# SAMA7D65_DDR3L.net
KiCad netlist of a schematic drawn in Altium Designer
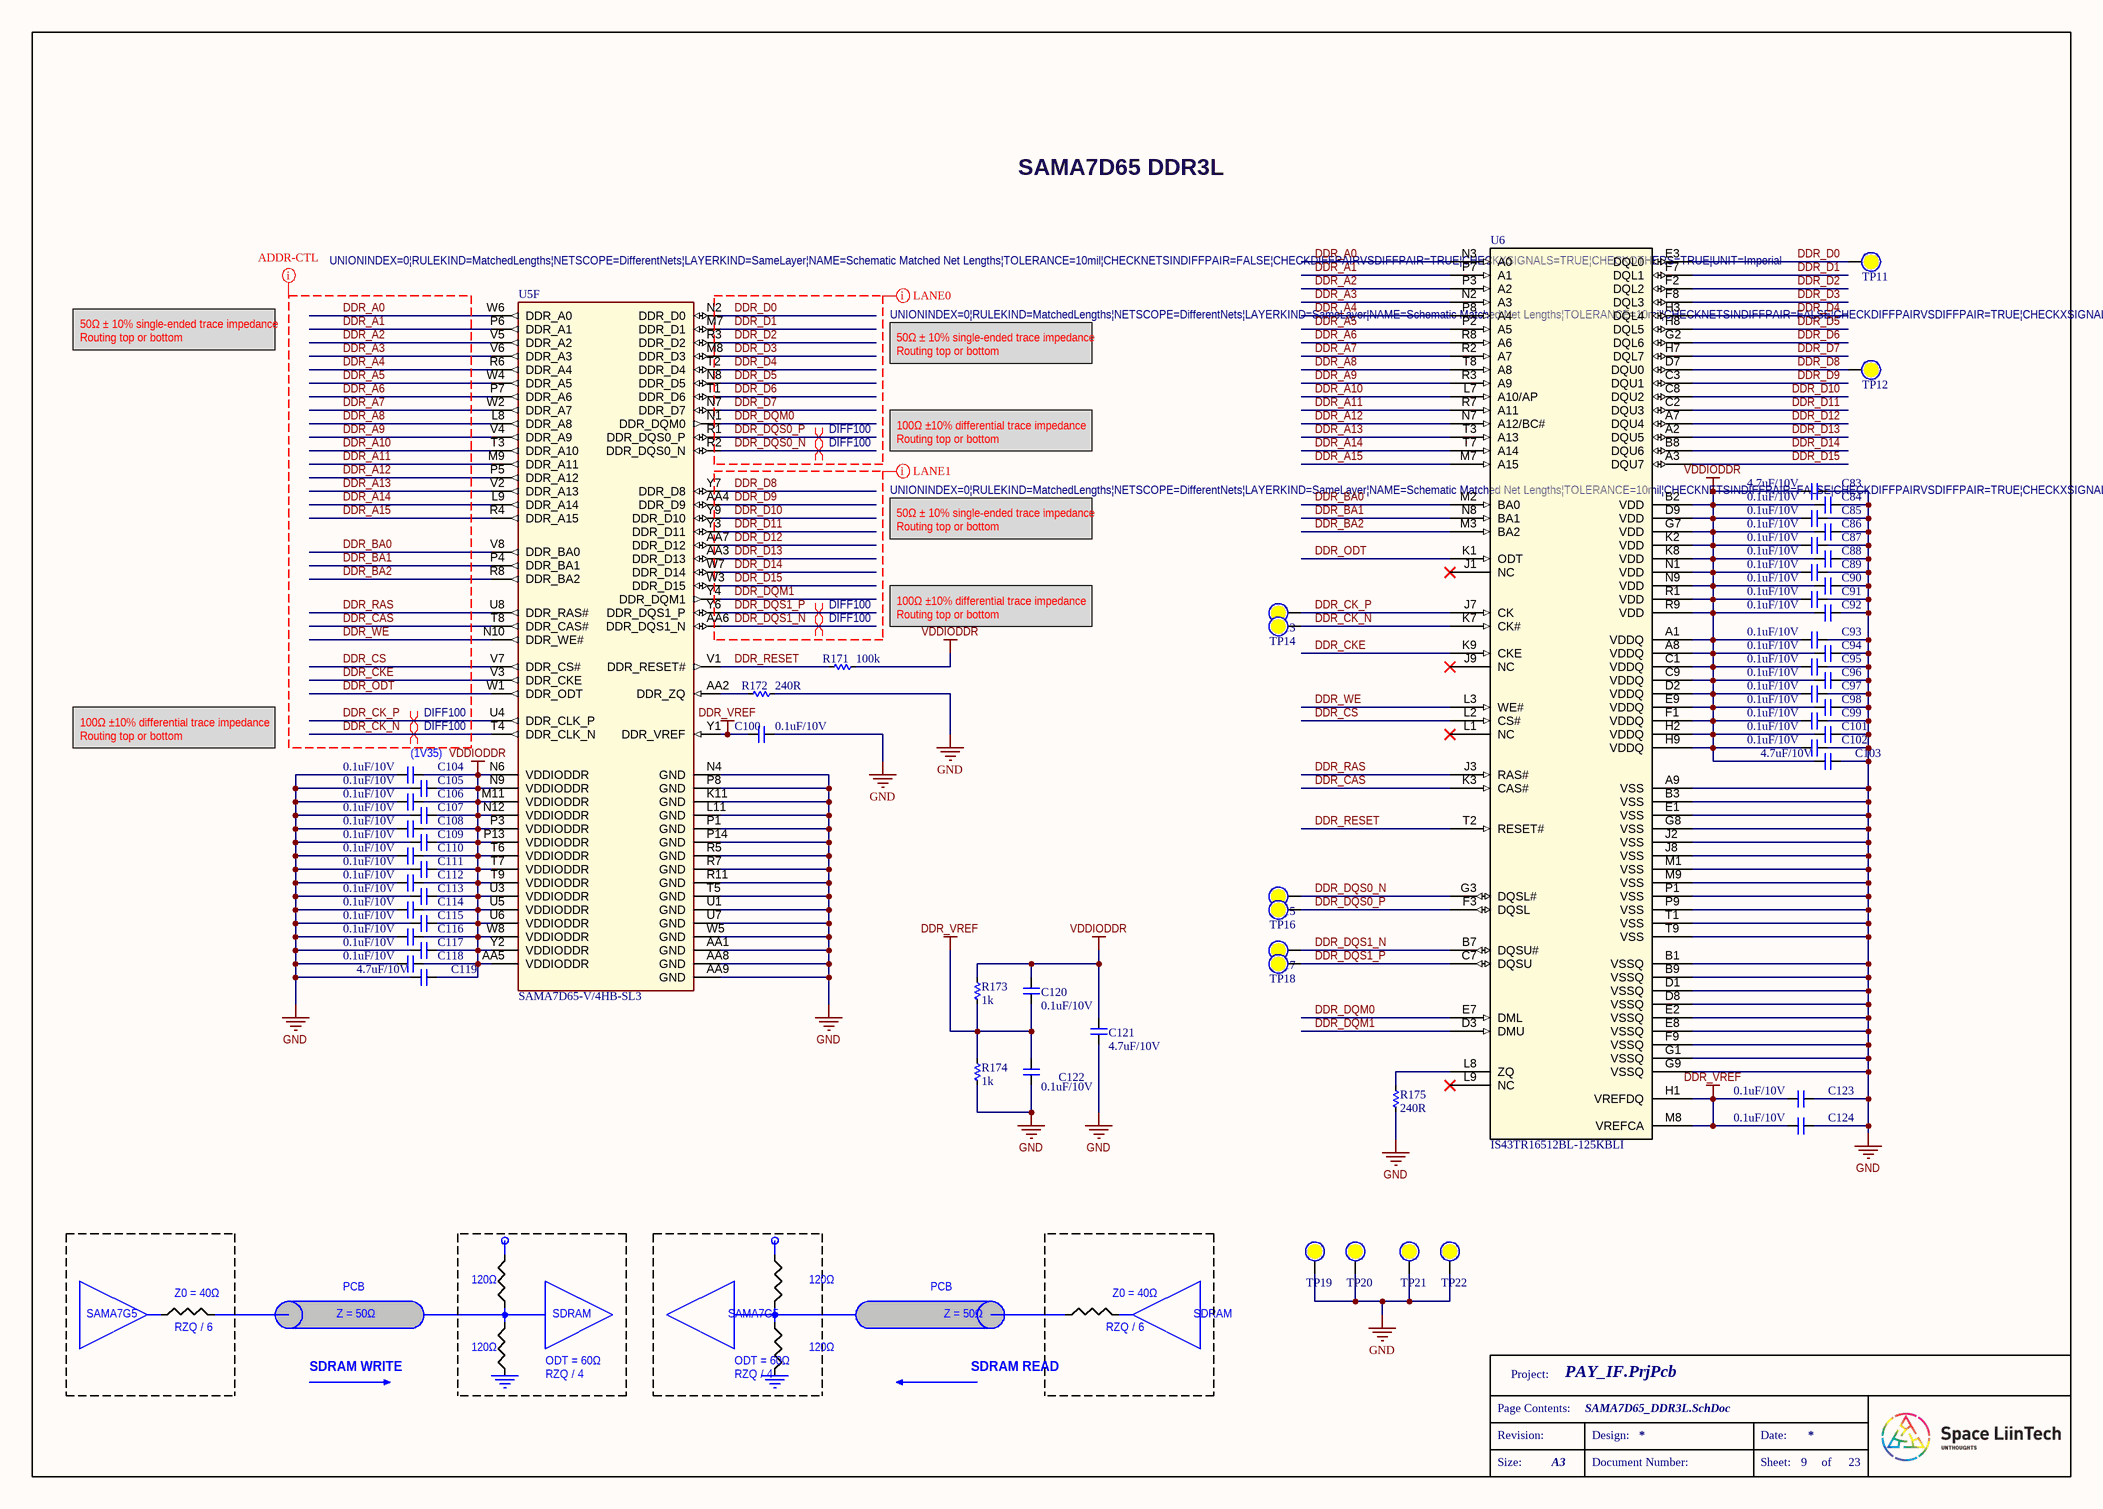
[diagram p0: SAMA7D65_DDR3L.SchDoc]

(export (version "E")
  (design (tool "Eeschema 10.0.6"))
  (components
    (comp (ref "C83")
      (value "4.7uF/10V")
      (footprint "CAP_C_1005X50_L")
      (description "CAP CHIP")
      (libsource (lib "IFBschelib") (part "_CAP_C_2"))
    )
    (comp (ref "C84")
      (value "0.1uF/10V")
      (footprint "CAP_C_0603x30")
      (description "CAP CHIP")
      (libsource (lib "IFBschelib") (part "_CAP_C_2"))
    )
    (comp (ref "C85")
      (value "0.1uF/10V")
      (footprint "CAP_C_0603x30")
      (description "CAP CHIP")
      (libsource (lib "IFBschelib") (part "_CAP_C_2"))
    )
    (comp (ref "C86")
      (value "0.1uF/10V")
      (footprint "CAP_C_0603x30")
      (description "CAP CHIP")
      (libsource (lib "IFBschelib") (part "_CAP_C_2"))
    )
    (comp (ref "C87")
      (value "0.1uF/10V")
      (footprint "CAP_C_0603x30")
      (description "CAP CHIP")
      (libsource (lib "IFBschelib") (part "_CAP_C_2"))
    )
    (comp (ref "C88")
      (value "0.1uF/10V")
      (footprint "CAP_C_0603x30")
      (description "CAP CHIP")
      (libsource (lib "IFBschelib") (part "_CAP_C_2"))
    )
    (comp (ref "C89")
      (value "0.1uF/10V")
      (footprint "CAP_C_0603x30")
      (description "CAP CHIP")
      (libsource (lib "IFBschelib") (part "_CAP_C_2"))
    )
    (comp (ref "C90")
      (value "0.1uF/10V")
      (footprint "CAP_C_0603x30")
      (description "CAP CHIP")
      (libsource (lib "IFBschelib") (part "_CAP_C_2"))
    )
    (comp (ref "C91")
      (value "0.1uF/10V")
      (footprint "CAP_C_0603x30")
      (description "CAP CHIP")
      (libsource (lib "IFBschelib") (part "_CAP_C_2"))
    )
    (comp (ref "C92")
      (value "0.1uF/10V")
      (footprint "CAP_C_0603x30")
      (description "CAP CHIP")
      (libsource (lib "IFBschelib") (part "_CAP_C_2"))
    )
    (comp (ref "C93")
      (value "0.1uF/10V")
      (footprint "CAP_C_0603x30")
      (description "CAP CHIP")
      (libsource (lib "IFBschelib") (part "_CAP_C_2"))
    )
    (comp (ref "C94")
      (value "0.1uF/10V")
      (footprint "CAP_C_0603x30")
      (description "CAP CHIP")
      (libsource (lib "IFBschelib") (part "_CAP_C_2"))
    )
    (comp (ref "C95")
      (value "0.1uF/10V")
      (footprint "CAP_C_0603x30")
      (description "CAP CHIP")
      (libsource (lib "IFBschelib") (part "_CAP_C_2"))
    )
    (comp (ref "C96")
      (value "0.1uF/10V")
      (footprint "CAP_C_0603x30")
      (description "CAP CHIP")
      (libsource (lib "IFBschelib") (part "_CAP_C_2"))
    )
    (comp (ref "C97")
      (value "0.1uF/10V")
      (footprint "CAP_C_0603x30")
      (description "CAP CHIP")
      (libsource (lib "IFBschelib") (part "_CAP_C_2"))
    )
    (comp (ref "C98")
      (value "0.1uF/10V")
      (footprint "CAP_C_0603x30")
      (description "CAP CHIP")
      (libsource (lib "IFBschelib") (part "_CAP_C_2"))
    )
    (comp (ref "C99")
      (value "0.1uF/10V")
      (footprint "CAP_C_0603x30")
      (description "CAP CHIP")
      (libsource (lib "IFBschelib") (part "_CAP_C_2"))
    )
    (comp (ref "C100")
      (value "0.1uF/10V")
      (footprint "CAP_C_0603x30")
      (description "CAP CHIP")
      (libsource (lib "IFBschelib") (part "_CAP_C_2"))
    )
    (comp (ref "C101")
      (value "0.1uF/10V")
      (footprint "CAP_C_0603x30")
      (description "CAP CHIP")
      (libsource (lib "IFBschelib") (part "_CAP_C_2"))
    )
    (comp (ref "C102")
      (value "0.1uF/10V")
      (footprint "CAP_C_0603x30")
      (description "CAP CHIP")
      (libsource (lib "IFBschelib") (part "_CAP_C_2"))
    )
    (comp (ref "C103")
      (value "4.7uF/10V")
      (footprint "CAP_C_1005X50_L")
      (description "CAP CHIP")
      (libsource (lib "IFBschelib") (part "_CAP_C_2"))
    )
    (comp (ref "C104")
      (value "0.1uF/10V")
      (footprint "CAP_C_0603x30")
      (description "CAP CHIP")
      (libsource (lib "IFBschelib") (part "_CAP_C_2"))
    )
    (comp (ref "C105")
      (value "0.1uF/10V")
      (footprint "CAP_C_0603x30")
      (description "CAP CHIP")
      (libsource (lib "IFBschelib") (part "_CAP_C_2"))
    )
    (comp (ref "C106")
      (value "0.1uF/10V")
      (footprint "CAP_C_0603x30")
      (description "CAP CHIP")
      (libsource (lib "IFBschelib") (part "_CAP_C_2"))
    )
    (comp (ref "C107")
      (value "0.1uF/10V")
      (footprint "CAP_C_0603x30")
      (description "CAP CHIP")
      (libsource (lib "IFBschelib") (part "_CAP_C_2"))
    )
    (comp (ref "C108")
      (value "0.1uF/10V")
      (footprint "CAP_C_0603x30")
      (description "CAP CHIP")
      (libsource (lib "IFBschelib") (part "_CAP_C_2"))
    )
    (comp (ref "C109")
      (value "0.1uF/10V")
      (footprint "CAP_C_0603x30")
      (description "CAP CHIP")
      (libsource (lib "IFBschelib") (part "_CAP_C_2"))
    )
    (comp (ref "C110")
      (value "0.1uF/10V")
      (footprint "CAP_C_0603x30")
      (description "CAP CHIP")
      (libsource (lib "IFBschelib") (part "_CAP_C_2"))
    )
    (comp (ref "C111")
      (value "0.1uF/10V")
      (footprint "CAP_C_0603x30")
      (description "CAP CHIP")
      (libsource (lib "IFBschelib") (part "_CAP_C_2"))
    )
    (comp (ref "C112")
      (value "0.1uF/10V")
      (footprint "CAP_C_0603x30")
      (description "CAP CHIP")
      (libsource (lib "IFBschelib") (part "_CAP_C_2"))
    )
    (comp (ref "C113")
      (value "0.1uF/10V")
      (footprint "CAP_C_0603x30")
      (description "CAP CHIP")
      (libsource (lib "IFBschelib") (part "_CAP_C_2"))
    )
    (comp (ref "C114")
      (value "0.1uF/10V")
      (footprint "CAP_C_0603x30")
      (description "CAP CHIP")
      (libsource (lib "IFBschelib") (part "_CAP_C_2"))
    )
    (comp (ref "C115")
      (value "0.1uF/10V")
      (footprint "CAP_C_0603x30")
      (description "CAP CHIP")
      (libsource (lib "IFBschelib") (part "_CAP_C_2"))
    )
    (comp (ref "C116")
      (value "0.1uF/10V")
      (footprint "CAP_C_0603x30")
      (description "CAP CHIP")
      (libsource (lib "IFBschelib") (part "_CAP_C_2"))
    )
    (comp (ref "C117")
      (value "0.1uF/10V")
      (footprint "CAP_C_0603x30")
      (description "CAP CHIP")
      (libsource (lib "IFBschelib") (part "_CAP_C_2"))
    )
    (comp (ref "C118")
      (value "0.1uF/10V")
      (footprint "CAP_C_0603x30")
      (description "CAP CHIP")
      (libsource (lib "IFBschelib") (part "_CAP_C_2"))
    )
    (comp (ref "C119")
      (value "4.7uF/10V")
      (footprint "CAP_C_1005X50_L")
      (description "CAP CHIP")
      (libsource (lib "IFBschelib") (part "_CAP_C_2"))
    )
    (comp (ref "C120")
      (value "0.1uF/10V")
      (footprint "CAP_C_0603x30")
      (description "CAP CHIP")
      (libsource (lib "IFBschelib") (part "_CAP_C_2"))
    )
    (comp (ref "C121")
      (value "4.7uF/10V")
      (footprint "CAP_C_1005X50_L")
      (description "CAP CHIP")
      (libsource (lib "IFBschelib") (part "_CAP_C_2"))
    )
    (comp (ref "C122")
      (value "0.1uF/10V")
      (footprint "CAP_C_0603x30")
      (description "CAP CHIP")
      (libsource (lib "IFBschelib") (part "_CAP_C_2"))
    )
    (comp (ref "C123")
      (value "0.1uF/10V")
      (footprint "CAP_C_0603x30")
      (description "CAP CHIP")
      (libsource (lib "IFBschelib") (part "_CAP_C_2"))
    )
    (comp (ref "C124")
      (value "0.1uF/10V")
      (footprint "CAP_C_0603x30")
      (description "CAP CHIP")
      (libsource (lib "IFBschelib") (part "_CAP_C_2"))
    )
    (comp (ref "R171")
      (value "100k")
      (footprint "RES_C_1005x30_L")
      (description "RES")
      (libsource (lib "IFBschelib") (part "_RES_B_2"))
    )
    (comp (ref "R172")
      (value "240R")
      (footprint "RES_C_0603X30")
      (description "RES")
      (libsource (lib "IFBschelib") (part "_RES_B_2"))
    )
    (comp (ref "R173")
      (value "1k")
      (footprint "RES_C_1005x30_L")
      (description "RES")
      (libsource (lib "IFBschelib") (part "_RES_B_2"))
    )
    (comp (ref "R174")
      (value "1k")
      (footprint "RES_C_1005x30_L")
      (description "RES")
      (libsource (lib "IFBschelib") (part "_RES_B_2"))
    )
    (comp (ref "R175")
      (value "240R")
      (footprint "RES_C_0603X30")
      (description "RES")
      (libsource (lib "IFBschelib") (part "_RES_B_2"))
    )
    (comp (ref "TP11")
      (value "~")
      (footprint "Test point")
      (description "Test Point")
      (libsource (lib "") (part "Test Point_2"))
    )
    (comp (ref "TP12")
      (value "~")
      (footprint "Test point")
      (description "Test Point")
      (libsource (lib "") (part "Test Point_2"))
    )
    (comp (ref "TP13")
      (value "~")
      (footprint "Test point")
      (description "Test Point")
      (libsource (lib "IFBschelib") (part "Test Point"))
    )
    (comp (ref "TP14")
      (value "~")
      (footprint "Test point")
      (description "Test Point")
      (libsource (lib "IFBschelib") (part "Test Point"))
    )
    (comp (ref "TP15")
      (value "~")
      (footprint "Test point")
      (description "Test Point")
      (libsource (lib "IFBschelib") (part "Test Point"))
    )
    (comp (ref "TP16")
      (value "~")
      (footprint "Test point")
      (description "Test Point")
      (libsource (lib "IFBschelib") (part "Test Point"))
    )
    (comp (ref "TP17")
      (value "~")
      (footprint "Test point")
      (description "Test Point")
      (libsource (lib "IFBschelib") (part "Test Point"))
    )
    (comp (ref "TP18")
      (value "~")
      (footprint "Test point")
      (description "Test Point")
      (libsource (lib "IFBschelib") (part "Test Point"))
    )
    (comp (ref "TP19")
      (value "~")
      (footprint "Test point")
      (description "Test Point")
      (libsource (lib "") (part "Test Point_1"))
    )
    (comp (ref "TP20")
      (value "~")
      (footprint "Test point")
      (description "Test Point")
      (libsource (lib "") (part "Test Point_1"))
    )
    (comp (ref "TP21")
      (value "~")
      (footprint "Test point")
      (description "Test Point")
      (libsource (lib "") (part "Test Point_1"))
    )
    (comp (ref "TP22")
      (value "~")
      (footprint "Test point")
      (description "Test Point")
      (libsource (lib "") (part "Test Point_1"))
    )
    (comp (ref "U5")
      (value "SAMA7D65-V/4HB-SL3")
      (footprint "TFBGA-343_14x14")
      (description "SAMA7D65 MPU 1000MHz Cortex-A7 TFBGA-343")
      (fields (field (name "Comment") "SAMA7D65") (field (name "OWNER") "Ciprian Abramov"))
      (libsource (lib "IFBschelib") (part "SAMA7D65"))
    )
    (comp (ref "U6")
      (value "IS43TR16512BL-125KBLI")
      (footprint "TWBGA96_ISI")
      (description "DDR3L")
      (fields (field (name "COPYRIGHT") "Copyright (C) 2025 Ultra Librarian. All rights reserved."))
      (libsource (lib "IFBschelib") (part "IC_RAM_IS43TR16512BL-125KBLI"))
    )
  )
  (nets
    (net (code "1") (name "/DDR_A0") (class "Default")
      (node (ref "U5") (pin "W6") (pinfunction "DDR_A0_W6") (pintype "output"))
      (node (ref "U6") (pin "N3") (pinfunction "A0_N3") (pintype "input"))
    )
    (net (code "2") (name "/DDR_A1") (class "Default")
      (node (ref "U5") (pin "P6") (pinfunction "DDR_A1_P6") (pintype "output"))
      (node (ref "U6") (pin "P7") (pinfunction "A1_P7") (pintype "input"))
    )
    (net (code "3") (name "/DDR_A2") (class "Default")
      (node (ref "U5") (pin "V5") (pinfunction "DDR_A2_V5") (pintype "output"))
      (node (ref "U6") (pin "P3") (pinfunction "A2_P3") (pintype "input"))
    )
    (net (code "4") (name "/DDR_A3") (class "Default")
      (node (ref "U5") (pin "V6") (pinfunction "DDR_A3_V6") (pintype "output"))
      (node (ref "U6") (pin "N2") (pinfunction "A3_N2") (pintype "input"))
    )
    (net (code "5") (name "/DDR_A4") (class "Default")
      (node (ref "U5") (pin "R6") (pinfunction "DDR_A4_R6") (pintype "output"))
      (node (ref "U6") (pin "P8") (pinfunction "A4_P8") (pintype "input"))
    )
    (net (code "6") (name "/DDR_A5") (class "Default")
      (node (ref "U5") (pin "W4") (pinfunction "DDR_A5_W4") (pintype "output"))
      (node (ref "U6") (pin "P2") (pinfunction "A5_P2") (pintype "input"))
    )
    (net (code "7") (name "/DDR_A6") (class "Default")
      (node (ref "U5") (pin "P7") (pinfunction "DDR_A6_P7") (pintype "output"))
      (node (ref "U6") (pin "R8") (pinfunction "A6_R8") (pintype "input"))
    )
    (net (code "8") (name "/DDR_A7") (class "Default")
      (node (ref "U5") (pin "W2") (pinfunction "DDR_A7_W2") (pintype "output"))
      (node (ref "U6") (pin "R2") (pinfunction "A7_R2") (pintype "input"))
    )
    (net (code "9") (name "/DDR_A8") (class "Default")
      (node (ref "U5") (pin "L8") (pinfunction "DDR_A8_L8") (pintype "output"))
      (node (ref "U6") (pin "T8") (pinfunction "A8_T8") (pintype "input"))
    )
    (net (code "10") (name "/DDR_A9") (class "Default")
      (node (ref "U5") (pin "V4") (pinfunction "DDR_A9_V4") (pintype "output"))
      (node (ref "U6") (pin "R3") (pinfunction "A9_R3") (pintype "input"))
    )
    (net (code "11") (name "/DDR_A10") (class "Default")
      (node (ref "U5") (pin "T3") (pinfunction "DDR_A10_T3") (pintype "output"))
      (node (ref "U6") (pin "L7") (pinfunction "A10/AP_L7") (pintype "input"))
    )
    (net (code "12") (name "/DDR_A11") (class "Default")
      (node (ref "U5") (pin "M9") (pinfunction "DDR_A11_M9") (pintype "output"))
      (node (ref "U6") (pin "R7") (pinfunction "A11_R7") (pintype "input"))
    )
    (net (code "13") (name "/DDR_A12") (class "Default")
      (node (ref "U5") (pin "P5") (pinfunction "DDR_A12_P5") (pintype "output"))
      (node (ref "U6") (pin "N7") (pinfunction "A12/BC#_N7") (pintype "input"))
    )
    (net (code "14") (name "/DDR_A13") (class "Default")
      (node (ref "U5") (pin "V2") (pinfunction "DDR_A13_V2") (pintype "output"))
      (node (ref "U6") (pin "T3") (pinfunction "A13_T3") (pintype "input"))
    )
    (net (code "15") (name "/DDR_A14") (class "Default")
      (node (ref "U5") (pin "L9") (pinfunction "DDR_A14_L9") (pintype "output"))
      (node (ref "U6") (pin "T7") (pinfunction "A14_T7") (pintype "input"))
    )
    (net (code "16") (name "/DDR_A15") (class "Default")
      (node (ref "U5") (pin "R4") (pinfunction "DDR_A15_R4") (pintype "output"))
      (node (ref "U6") (pin "M7") (pinfunction "A15_M7") (pintype "input"))
    )
    (net (code "17") (name "/DDR_BA0") (class "Default")
      (node (ref "U5") (pin "V8") (pinfunction "DDR_BA0_V8") (pintype "output"))
      (node (ref "U6") (pin "M2") (pinfunction "BA0_M2") (pintype "input"))
    )
    (net (code "18") (name "/DDR_BA1") (class "Default")
      (node (ref "U5") (pin "P4") (pinfunction "DDR_BA1_P4") (pintype "output"))
      (node (ref "U6") (pin "N8") (pinfunction "BA1_N8") (pintype "input"))
    )
    (net (code "19") (name "/DDR_BA2") (class "Default")
      (node (ref "U5") (pin "R8") (pinfunction "DDR_BA2_R8") (pintype "output"))
      (node (ref "U6") (pin "M3") (pinfunction "BA2_M3") (pintype "input"))
    )
    (net (code "20") (name "/DDR_CAS") (class "Default")
      (node (ref "U5") (pin "T8") (pinfunction "DDR_CAS#_T8") (pintype "output"))
      (node (ref "U6") (pin "K3") (pinfunction "CAS#_K3") (pintype "input"))
    )
    (net (code "21") (name "/DDR_CKE") (class "Default")
      (node (ref "U5") (pin "V3") (pinfunction "DDR_CKE_V3") (pintype "output"))
      (node (ref "U6") (pin "K9") (pinfunction "CKE_K9") (pintype "input"))
    )
    (net (code "22") (name "/DDR_CK_N") (class "Default")
      (node (ref "TP14") (pin "0") (pinfunction "0_0") (pintype "passive"))
      (node (ref "U5") (pin "T4") (pinfunction "DDR_CLK_N_T4") (pintype "output"))
      (node (ref "U6") (pin "K7") (pinfunction "CK#_K7") (pintype "input"))
    )
    (net (code "23") (name "/DDR_CK_P") (class "Default")
      (node (ref "TP13") (pin "0") (pinfunction "0_0") (pintype "passive"))
      (node (ref "U5") (pin "U4") (pinfunction "DDR_CLK_P_U4") (pintype "output"))
      (node (ref "U6") (pin "J7") (pinfunction "CK_J7") (pintype "input"))
    )
    (net (code "24") (name "/DDR_CS") (class "Default")
      (node (ref "U5") (pin "V7") (pinfunction "DDR_CS#_V7") (pintype "output"))
      (node (ref "U6") (pin "L2") (pinfunction "CS#_L2") (pintype "input"))
    )
    (net (code "25") (name "/DDR_D0") (class "Default")
      (node (ref "TP11") (pin "0") (pinfunction "0_0") (pintype "passive"))
      (node (ref "U5") (pin "N2") (pinfunction "DDR_D0_N2") (pintype "bidirectional"))
      (node (ref "U6") (pin "E3") (pinfunction "DQL0_E3") (pintype "bidirectional"))
    )
    (net (code "26") (name "/DDR_D1") (class "Default")
      (node (ref "U5") (pin "M7") (pinfunction "DDR_D1_M7") (pintype "bidirectional"))
      (node (ref "U6") (pin "F7") (pinfunction "DQL1_F7") (pintype "bidirectional"))
    )
    (net (code "27") (name "/DDR_D2") (class "Default")
      (node (ref "U5") (pin "R3") (pinfunction "DDR_D2_R3") (pintype "bidirectional"))
      (node (ref "U6") (pin "F2") (pinfunction "DQL2_F2") (pintype "bidirectional"))
    )
    (net (code "28") (name "/DDR_D3") (class "Default")
      (node (ref "U5") (pin "M8") (pinfunction "DDR_D3_M8") (pintype "bidirectional"))
      (node (ref "U6") (pin "F8") (pinfunction "DQL3_F8") (pintype "bidirectional"))
    )
    (net (code "29") (name "/DDR_D4") (class "Default")
      (node (ref "U5") (pin "T2") (pinfunction "DDR_D4_T2") (pintype "bidirectional"))
      (node (ref "U6") (pin "H3") (pinfunction "DQL4_H3") (pintype "bidirectional"))
    )
    (net (code "30") (name "/DDR_D5") (class "Default")
      (node (ref "U5") (pin "N8") (pinfunction "DDR_D5_N8") (pintype "bidirectional"))
      (node (ref "U6") (pin "H8") (pinfunction "DQL5_H8") (pintype "bidirectional"))
    )
    (net (code "31") (name "/DDR_D6") (class "Default")
      (node (ref "U5") (pin "T1") (pinfunction "DDR_D6_T1") (pintype "bidirectional"))
      (node (ref "U6") (pin "G2") (pinfunction "DQL6_G2") (pintype "bidirectional"))
    )
    (net (code "32") (name "/DDR_D7") (class "Default")
      (node (ref "U5") (pin "N7") (pinfunction "DDR_D7_N7") (pintype "bidirectional"))
      (node (ref "U6") (pin "H7") (pinfunction "DQL7_H7") (pintype "bidirectional"))
    )
    (net (code "33") (name "/DDR_D8") (class "Default")
      (node (ref "TP12") (pin "0") (pinfunction "0_0") (pintype "passive"))
      (node (ref "U5") (pin "Y7") (pinfunction "DDR_D8_Y7") (pintype "bidirectional"))
      (node (ref "U6") (pin "D7") (pinfunction "DQU0_D7") (pintype "bidirectional"))
    )
    (net (code "34") (name "/DDR_D9") (class "Default")
      (node (ref "U5") (pin "AA4") (pinfunction "DDR_D9_AA4") (pintype "bidirectional"))
      (node (ref "U6") (pin "C3") (pinfunction "DQU1_C3") (pintype "bidirectional"))
    )
    (net (code "35") (name "/DDR_D10") (class "Default")
      (node (ref "U5") (pin "Y9") (pinfunction "DDR_D10_Y9") (pintype "bidirectional"))
      (node (ref "U6") (pin "C8") (pinfunction "DQU2_C8") (pintype "bidirectional"))
    )
    (net (code "36") (name "/DDR_D11") (class "Default")
      (node (ref "U5") (pin "Y3") (pinfunction "DDR_D11_Y3") (pintype "bidirectional"))
      (node (ref "U6") (pin "C2") (pinfunction "DQU3_C2") (pintype "bidirectional"))
    )
    (net (code "37") (name "/DDR_D12") (class "Default")
      (node (ref "U5") (pin "AA7") (pinfunction "DDR_D12_AA7") (pintype "bidirectional"))
      (node (ref "U6") (pin "A7") (pinfunction "DQU4_A7") (pintype "bidirectional"))
    )
    (net (code "38") (name "/DDR_D13") (class "Default")
      (node (ref "U5") (pin "AA3") (pinfunction "DDR_D13_AA3") (pintype "bidirectional"))
      (node (ref "U6") (pin "A2") (pinfunction "DQU5_A2") (pintype "bidirectional"))
    )
    (net (code "39") (name "/DDR_D14") (class "Default")
      (node (ref "U5") (pin "W7") (pinfunction "DDR_D14_W7") (pintype "bidirectional"))
      (node (ref "U6") (pin "B8") (pinfunction "DQU6_B8") (pintype "bidirectional"))
    )
    (net (code "40") (name "/DDR_D15") (class "Default")
      (node (ref "U5") (pin "W3") (pinfunction "DDR_D15_W3") (pintype "bidirectional"))
      (node (ref "U6") (pin "A3") (pinfunction "DQU7_A3") (pintype "bidirectional"))
    )
    (net (code "41") (name "/DDR_DQM0") (class "Default")
      (node (ref "U5") (pin "N1") (pinfunction "DDR_DQM0_N1") (pintype "output"))
      (node (ref "U6") (pin "E7") (pinfunction "DML_E7") (pintype "input"))
    )
    (net (code "42") (name "/DDR_DQM1") (class "Default")
      (node (ref "U5") (pin "Y4") (pinfunction "DDR_DQM1_Y4") (pintype "output"))
      (node (ref "U6") (pin "D3") (pinfunction "DMU_D3") (pintype "input"))
    )
    (net (code "43") (name "/DDR_DQS0_N") (class "Default")
      (node (ref "TP15") (pin "0") (pinfunction "0_0") (pintype "passive"))
      (node (ref "U5") (pin "R2") (pinfunction "DDR_DQS0_N_R2") (pintype "bidirectional"))
      (node (ref "U6") (pin "G3") (pinfunction "DQSL#_G3") (pintype "bidirectional"))
    )
    (net (code "44") (name "/DDR_DQS0_P") (class "Default")
      (node (ref "TP16") (pin "0") (pinfunction "0_0") (pintype "passive"))
      (node (ref "U5") (pin "R1") (pinfunction "DDR_DQS0_P_R1") (pintype "bidirectional"))
      (node (ref "U6") (pin "F3") (pinfunction "DQSL_F3") (pintype "bidirectional"))
    )
    (net (code "45") (name "/DDR_DQS1_N") (class "Default")
      (node (ref "TP17") (pin "0") (pinfunction "0_0") (pintype "passive"))
      (node (ref "U5") (pin "AA6") (pinfunction "DDR_DQS1_N_AA6") (pintype "bidirectional"))
      (node (ref "U6") (pin "B7") (pinfunction "DQSU#_B7") (pintype "bidirectional"))
    )
    (net (code "46") (name "/DDR_DQS1_P") (class "Default")
      (node (ref "TP18") (pin "0") (pinfunction "0_0") (pintype "passive"))
      (node (ref "U5") (pin "Y6") (pinfunction "DDR_DQS1_P_Y6") (pintype "bidirectional"))
      (node (ref "U6") (pin "C7") (pinfunction "DQSU_C7") (pintype "bidirectional"))
    )
    (net (code "47") (name "/DDR_ODT") (class "Default")
      (node (ref "U5") (pin "W1") (pinfunction "DDR_ODT_W1") (pintype "output"))
      (node (ref "U6") (pin "K1") (pinfunction "ODT_K1") (pintype "input"))
    )
    (net (code "48") (name "/DDR_RAS") (class "Default")
      (node (ref "U5") (pin "U8") (pinfunction "DDR_RAS#_U8") (pintype "output"))
      (node (ref "U6") (pin "J3") (pinfunction "RAS#_J3") (pintype "input"))
    )
    (net (code "49") (name "/DDR_RESET") (class "Default")
      (node (ref "R171") (pin "1") (pinfunction "1_1") (pintype "passive"))
      (node (ref "U5") (pin "V1") (pinfunction "DDR_RESET#_V1") (pintype "output"))
      (node (ref "U6") (pin "T2") (pinfunction "RESET#_T2") (pintype "input"))
    )
    (net (code "50") (name "/DDR_WE") (class "Default")
      (node (ref "U5") (pin "N10") (pinfunction "DDR_WE#_N10") (pintype "output"))
      (node (ref "U6") (pin "L3") (pinfunction "WE#_L3") (pintype "input"))
    )
    (net (code "51") (name "DDR_VREF") (class "Default")
      (node (ref "C100") (pin "1") (pinfunction "1_1") (pintype "passive"))
      (node (ref "C120") (pin "1") (pinfunction "1_1") (pintype "passive"))
      (node (ref "C122") (pin "2") (pinfunction "2_2") (pintype "passive"))
      (node (ref "C123") (pin "1") (pinfunction "1_1") (pintype "passive"))
      (node (ref "C124") (pin "1") (pinfunction "1_1") (pintype "passive"))
      (node (ref "R173") (pin "1") (pinfunction "1_1") (pintype "passive"))
      (node (ref "R174") (pin "2") (pinfunction "2_2") (pintype "passive"))
      (node (ref "U5") (pin "Y1") (pinfunction "DDR_VREF_Y1") (pintype "input"))
      (node (ref "U6") (pin "H1") (pinfunction "VREFDQ_H1") (pintype "power_in"))
      (node (ref "U6") (pin "M8") (pinfunction "VREFCA_M8") (pintype "power_in"))
    )
    (net (code "52") (name "GND") (class "Default")
      (node (ref "C100") (pin "2") (pinfunction "2_2") (pintype "passive"))
      (node (ref "C101") (pin "2") (pinfunction "2_2") (pintype "passive"))
      (node (ref "C102") (pin "2") (pinfunction "2_2") (pintype "passive"))
      (node (ref "C103") (pin "2") (pinfunction "2_2") (pintype "passive"))
      (node (ref "C104") (pin "1") (pinfunction "1_1") (pintype "passive"))
      (node (ref "C105") (pin "1") (pinfunction "1_1") (pintype "passive"))
      (node (ref "C106") (pin "1") (pinfunction "1_1") (pintype "passive"))
      (node (ref "C107") (pin "1") (pinfunction "1_1") (pintype "passive"))
      (node (ref "C108") (pin "1") (pinfunction "1_1") (pintype "passive"))
      (node (ref "C109") (pin "1") (pinfunction "1_1") (pintype "passive"))
      (node (ref "C110") (pin "1") (pinfunction "1_1") (pintype "passive"))
      (node (ref "C111") (pin "1") (pinfunction "1_1") (pintype "passive"))
      (node (ref "C112") (pin "1") (pinfunction "1_1") (pintype "passive"))
      (node (ref "C113") (pin "1") (pinfunction "1_1") (pintype "passive"))
      (node (ref "C114") (pin "1") (pinfunction "1_1") (pintype "passive"))
      (node (ref "C115") (pin "1") (pinfunction "1_1") (pintype "passive"))
      (node (ref "C116") (pin "1") (pinfunction "1_1") (pintype "passive"))
      (node (ref "C117") (pin "1") (pinfunction "1_1") (pintype "passive"))
      (node (ref "C118") (pin "1") (pinfunction "1_1") (pintype "passive"))
      (node (ref "C119") (pin "1") (pinfunction "1_1") (pintype "passive"))
      (node (ref "C121") (pin "1") (pinfunction "1_1") (pintype "passive"))
      (node (ref "C122") (pin "1") (pinfunction "1_1") (pintype "passive"))
      (node (ref "C123") (pin "2") (pinfunction "2_2") (pintype "passive"))
      (node (ref "C124") (pin "2") (pinfunction "2_2") (pintype "passive"))
      (node (ref "C83") (pin "2") (pinfunction "2_2") (pintype "passive"))
      (node (ref "C84") (pin "2") (pinfunction "2_2") (pintype "passive"))
      (node (ref "C85") (pin "2") (pinfunction "2_2") (pintype "passive"))
      (node (ref "C86") (pin "2") (pinfunction "2_2") (pintype "passive"))
      (node (ref "C87") (pin "2") (pinfunction "2_2") (pintype "passive"))
      (node (ref "C88") (pin "2") (pinfunction "2_2") (pintype "passive"))
      (node (ref "C89") (pin "2") (pinfunction "2_2") (pintype "passive"))
      (node (ref "C90") (pin "2") (pinfunction "2_2") (pintype "passive"))
      (node (ref "C91") (pin "2") (pinfunction "2_2") (pintype "passive"))
      (node (ref "C92") (pin "2") (pinfunction "2_2") (pintype "passive"))
      (node (ref "C93") (pin "2") (pinfunction "2_2") (pintype "passive"))
      (node (ref "C94") (pin "2") (pinfunction "2_2") (pintype "passive"))
      (node (ref "C95") (pin "2") (pinfunction "2_2") (pintype "passive"))
      (node (ref "C96") (pin "2") (pinfunction "2_2") (pintype "passive"))
      (node (ref "C97") (pin "2") (pinfunction "2_2") (pintype "passive"))
      (node (ref "C98") (pin "2") (pinfunction "2_2") (pintype "passive"))
      (node (ref "C99") (pin "2") (pinfunction "2_2") (pintype "passive"))
      (node (ref "R172") (pin "2") (pinfunction "2_2") (pintype "passive"))
      (node (ref "R174") (pin "1") (pinfunction "1_1") (pintype "passive"))
      (node (ref "R175") (pin "1") (pinfunction "1_1") (pintype "passive"))
      (node (ref "TP19") (pin "0") (pinfunction "0_0") (pintype "passive"))
      (node (ref "TP20") (pin "0") (pinfunction "0_0") (pintype "passive"))
      (node (ref "TP21") (pin "0") (pinfunction "0_0") (pintype "passive"))
      (node (ref "TP22") (pin "0") (pinfunction "0_0") (pintype "passive"))
      (node (ref "U5") (pin "AA1") (pinfunction "GND_AA1") (pintype "power_in"))
      (node (ref "U5") (pin "AA8") (pinfunction "GND_AA8") (pintype "power_in"))
      (node (ref "U5") (pin "AA9") (pinfunction "GND_AA9") (pintype "power_in"))
      (node (ref "U5") (pin "K11") (pinfunction "GND_K11") (pintype "power_in"))
      (node (ref "U5") (pin "L11") (pinfunction "GND_L11") (pintype "power_in"))
      (node (ref "U5") (pin "N4") (pinfunction "GND_N4") (pintype "power_in"))
      (node (ref "U5") (pin "P1") (pinfunction "GND_P1") (pintype "power_in"))
      (node (ref "U5") (pin "P14") (pinfunction "GND_P14") (pintype "power_in"))
      (node (ref "U5") (pin "P8") (pinfunction "GND_P8") (pintype "power_in"))
      (node (ref "U5") (pin "R11") (pinfunction "GND_R11") (pintype "power_in"))
      (node (ref "U5") (pin "R5") (pinfunction "GND_R5") (pintype "power_in"))
      (node (ref "U5") (pin "R7") (pinfunction "GND_R7") (pintype "power_in"))
      (node (ref "U5") (pin "T5") (pinfunction "GND_T5") (pintype "power_in"))
      (node (ref "U5") (pin "U1") (pinfunction "GND_U1") (pintype "power_in"))
      (node (ref "U5") (pin "U7") (pinfunction "GND_U7") (pintype "power_in"))
      (node (ref "U5") (pin "W5") (pinfunction "GND_W5") (pintype "power_in"))
      (node (ref "U6") (pin "A9") (pinfunction "VSS_A9") (pintype "power_in"))
      (node (ref "U6") (pin "B1") (pinfunction "VSSQ_B1") (pintype "power_in"))
      (node (ref "U6") (pin "B3") (pinfunction "VSS_B3") (pintype "power_in"))
      (node (ref "U6") (pin "B9") (pinfunction "VSSQ_B9") (pintype "power_in"))
      (node (ref "U6") (pin "D1") (pinfunction "VSSQ_D1") (pintype "power_in"))
      (node (ref "U6") (pin "D8") (pinfunction "VSSQ_D8") (pintype "power_in"))
      (node (ref "U6") (pin "E1") (pinfunction "VSS_E1") (pintype "power_in"))
      (node (ref "U6") (pin "E2") (pinfunction "VSSQ_E2") (pintype "power_in"))
      (node (ref "U6") (pin "E8") (pinfunction "VSSQ_E8") (pintype "power_in"))
      (node (ref "U6") (pin "F9") (pinfunction "VSSQ_F9") (pintype "power_in"))
      (node (ref "U6") (pin "G1") (pinfunction "VSSQ_G1") (pintype "power_in"))
      (node (ref "U6") (pin "G8") (pinfunction "VSS_G8") (pintype "power_in"))
      (node (ref "U6") (pin "G9") (pinfunction "VSSQ_G9") (pintype "power_in"))
      (node (ref "U6") (pin "J2") (pinfunction "VSS_J2") (pintype "power_in"))
      (node (ref "U6") (pin "J8") (pinfunction "VSS_J8") (pintype "power_in"))
      (node (ref "U6") (pin "M1") (pinfunction "VSS_M1") (pintype "power_in"))
      (node (ref "U6") (pin "M9") (pinfunction "VSS_M9") (pintype "power_in"))
      (node (ref "U6") (pin "P1") (pinfunction "VSS_P1") (pintype "power_in"))
      (node (ref "U6") (pin "P9") (pinfunction "VSS_P9") (pintype "power_in"))
      (node (ref "U6") (pin "T1") (pinfunction "VSS_T1") (pintype "power_in"))
      (node (ref "U6") (pin "T9") (pinfunction "VSS_T9") (pintype "power_in"))
    )
    (net (code "53") (name "Net-(U5F-DDR_ZQ)") (class "Default")
      (node (ref "R172") (pin "1") (pinfunction "1_1") (pintype "passive"))
      (node (ref "U5") (pin "AA2") (pinfunction "DDR_ZQ_AA2") (pintype "input"))
    )
    (net (code "54") (name "Net-(U6-ZQ)") (class "Default")
      (node (ref "R175") (pin "2") (pinfunction "2_2") (pintype "passive"))
      (node (ref "U6") (pin "L8") (pinfunction "ZQ_L8") (pintype "power_in"))
    )
    (net (code "55") (name "VDDIODDR") (class "Default")
      (node (ref "C101") (pin "1") (pinfunction "1_1") (pintype "passive"))
      (node (ref "C102") (pin "1") (pinfunction "1_1") (pintype "passive"))
      (node (ref "C103") (pin "1") (pinfunction "1_1") (pintype "passive"))
      (node (ref "C104") (pin "2") (pinfunction "2_2") (pintype "passive"))
      (node (ref "C105") (pin "2") (pinfunction "2_2") (pintype "passive"))
      (node (ref "C106") (pin "2") (pinfunction "2_2") (pintype "passive"))
      (node (ref "C107") (pin "2") (pinfunction "2_2") (pintype "passive"))
      (node (ref "C108") (pin "2") (pinfunction "2_2") (pintype "passive"))
      (node (ref "C109") (pin "2") (pinfunction "2_2") (pintype "passive"))
      (node (ref "C110") (pin "2") (pinfunction "2_2") (pintype "passive"))
      (node (ref "C111") (pin "2") (pinfunction "2_2") (pintype "passive"))
      (node (ref "C112") (pin "2") (pinfunction "2_2") (pintype "passive"))
      (node (ref "C113") (pin "2") (pinfunction "2_2") (pintype "passive"))
      (node (ref "C114") (pin "2") (pinfunction "2_2") (pintype "passive"))
      (node (ref "C115") (pin "2") (pinfunction "2_2") (pintype "passive"))
      (node (ref "C116") (pin "2") (pinfunction "2_2") (pintype "passive"))
      (node (ref "C117") (pin "2") (pinfunction "2_2") (pintype "passive"))
      (node (ref "C118") (pin "2") (pinfunction "2_2") (pintype "passive"))
      (node (ref "C119") (pin "2") (pinfunction "2_2") (pintype "passive"))
      (node (ref "C120") (pin "2") (pinfunction "2_2") (pintype "passive"))
      (node (ref "C121") (pin "2") (pinfunction "2_2") (pintype "passive"))
      (node (ref "C83") (pin "1") (pinfunction "1_1") (pintype "passive"))
      (node (ref "C84") (pin "1") (pinfunction "1_1") (pintype "passive"))
      (node (ref "C85") (pin "1") (pinfunction "1_1") (pintype "passive"))
      (node (ref "C86") (pin "1") (pinfunction "1_1") (pintype "passive"))
      (node (ref "C87") (pin "1") (pinfunction "1_1") (pintype "passive"))
      (node (ref "C88") (pin "1") (pinfunction "1_1") (pintype "passive"))
      (node (ref "C89") (pin "1") (pinfunction "1_1") (pintype "passive"))
      (node (ref "C90") (pin "1") (pinfunction "1_1") (pintype "passive"))
      (node (ref "C91") (pin "1") (pinfunction "1_1") (pintype "passive"))
      (node (ref "C92") (pin "1") (pinfunction "1_1") (pintype "passive"))
      (node (ref "C93") (pin "1") (pinfunction "1_1") (pintype "passive"))
      (node (ref "C94") (pin "1") (pinfunction "1_1") (pintype "passive"))
      (node (ref "C95") (pin "1") (pinfunction "1_1") (pintype "passive"))
      (node (ref "C96") (pin "1") (pinfunction "1_1") (pintype "passive"))
      (node (ref "C97") (pin "1") (pinfunction "1_1") (pintype "passive"))
      (node (ref "C98") (pin "1") (pinfunction "1_1") (pintype "passive"))
      (node (ref "C99") (pin "1") (pinfunction "1_1") (pintype "passive"))
      (node (ref "R171") (pin "2") (pinfunction "2_2") (pintype "passive"))
      (node (ref "R173") (pin "2") (pinfunction "2_2") (pintype "passive"))
      (node (ref "U5") (pin "AA5") (pinfunction "VDDIODDR_AA5") (pintype "power_in"))
      (node (ref "U5") (pin "M11") (pinfunction "VDDIODDR_M11") (pintype "power_in"))
      (node (ref "U5") (pin "N12") (pinfunction "VDDIODDR_N12") (pintype "power_in"))
      (node (ref "U5") (pin "N6") (pinfunction "VDDIODDR_N6") (pintype "power_in"))
      (node (ref "U5") (pin "N9") (pinfunction "VDDIODDR_N9") (pintype "power_in"))
      (node (ref "U5") (pin "P13") (pinfunction "VDDIODDR_P13") (pintype "power_in"))
      (node (ref "U5") (pin "P3") (pinfunction "VDDIODDR_P3") (pintype "power_in"))
      (node (ref "U5") (pin "T6") (pinfunction "VDDIODDR_T6") (pintype "power_in"))
      (node (ref "U5") (pin "T7") (pinfunction "VDDIODDR_T7") (pintype "power_in"))
      (node (ref "U5") (pin "T9") (pinfunction "VDDIODDR_T9") (pintype "power_in"))
      (node (ref "U5") (pin "U3") (pinfunction "VDDIODDR_U3") (pintype "power_in"))
      (node (ref "U5") (pin "U5") (pinfunction "VDDIODDR_U5") (pintype "power_in"))
      (node (ref "U5") (pin "U6") (pinfunction "VDDIODDR_U6") (pintype "power_in"))
      (node (ref "U5") (pin "W8") (pinfunction "VDDIODDR_W8") (pintype "power_in"))
      (node (ref "U5") (pin "Y2") (pinfunction "VDDIODDR_Y2") (pintype "power_in"))
      (node (ref "U6") (pin "A1") (pinfunction "VDDQ_A1") (pintype "power_in"))
      (node (ref "U6") (pin "A8") (pinfunction "VDDQ_A8") (pintype "power_in"))
      (node (ref "U6") (pin "B2") (pinfunction "VDD_B2") (pintype "power_in"))
      (node (ref "U6") (pin "C1") (pinfunction "VDDQ_C1") (pintype "power_in"))
      (node (ref "U6") (pin "C9") (pinfunction "VDDQ_C9") (pintype "power_in"))
      (node (ref "U6") (pin "D2") (pinfunction "VDDQ_D2") (pintype "power_in"))
      (node (ref "U6") (pin "D9") (pinfunction "VDD_D9") (pintype "power_in"))
      (node (ref "U6") (pin "E9") (pinfunction "VDDQ_E9") (pintype "power_in"))
      (node (ref "U6") (pin "F1") (pinfunction "VDDQ_F1") (pintype "power_in"))
      (node (ref "U6") (pin "G7") (pinfunction "VDD_G7") (pintype "power_in"))
      (node (ref "U6") (pin "H2") (pinfunction "VDDQ_H2") (pintype "power_in"))
      (node (ref "U6") (pin "H9") (pinfunction "VDDQ_H9") (pintype "power_in"))
      (node (ref "U6") (pin "K2") (pinfunction "VDD_K2") (pintype "power_in"))
      (node (ref "U6") (pin "K8") (pinfunction "VDD_K8") (pintype "power_in"))
      (node (ref "U6") (pin "N1") (pinfunction "VDD_N1") (pintype "power_in"))
      (node (ref "U6") (pin "N9") (pinfunction "VDD_N9") (pintype "power_in"))
      (node (ref "U6") (pin "R1") (pinfunction "VDD_R1") (pintype "power_in"))
      (node (ref "U6") (pin "R9") (pinfunction "VDD_R9") (pintype "power_in"))
    )
    (net (code "56") (name "unconnected-(U6-NC-PadJ1)") (class "Default")
      (node (ref "U6") (pin "J1") (pinfunction "NC_J1") (pintype "passive+no_connect"))
    )
    (net (code "57") (name "unconnected-(U6-NC-PadJ9)") (class "Default")
      (node (ref "U6") (pin "J9") (pinfunction "NC_J9") (pintype "passive+no_connect"))
    )
    (net (code "58") (name "unconnected-(U6-NC-PadL1)") (class "Default")
      (node (ref "U6") (pin "L1") (pinfunction "NC_L1") (pintype "passive+no_connect"))
    )
    (net (code "59") (name "unconnected-(U6-NC-PadL9)") (class "Default")
      (node (ref "U6") (pin "L9") (pinfunction "NC_L9") (pintype "passive+no_connect"))
    )
  )
)
